# 5V_Source.net
KiCad netlist of a schematic drawn in Altium Designer
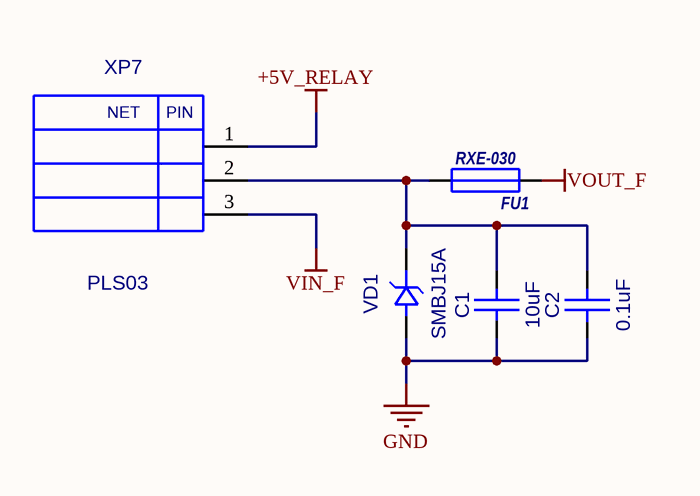
[diagram p0: 5V_Source.SchDoc]

(export (version "E")
  (design (tool "Eeschema 10.0.6"))
  (components
    (comp (ref "C1")
      (value "10uF")
      (footprint "CC0805")
      (description "CC0805")
      (libsource (lib "gprs_modem_2") (part "CC0805"))
    )
    (comp (ref "C2")
      (value "0.1uF")
      (footprint "CC0603")
      (description "CC0603")
      (libsource (lib "gprs_modem_2") (part "CC0603"))
    )
    (comp (ref "FU1")
      (value "RXE-030")
      (footprint "RXE-110")
      (description "RXE-110")
      (libsource (lib "gprs_modem_2") (part "RXE-110"))
    )
    (comp (ref "VD1")
      (value "SMBJ15A")
      (footprint "SMB")
      (description "SMBJ")
      (libsource (lib "gprs_modem_2") (part "SMBJ"))
    )
    (comp (ref "XP7") (value "PLS03") (footprint "PLS-03") (libsource (lib "gprs_modem_2") (part "PLS03")))
  )
  (nets
    (net (code "1") (name "+5V_RELAY") (class "Default")
      (node (ref "XP7") (pin "1") (pinfunction "1_1") (pintype "passive"))
    )
    (net (code "2") (name "GND") (class "Default")
      (node (ref "C1") (pin "1") (pinfunction "A_1") (pintype "passive"))
      (node (ref "C2") (pin "1") (pinfunction "A_1") (pintype "passive"))
      (node (ref "VD1") (pin "1") (pinfunction "A_1") (pintype "passive"))
    )
    (net (code "3") (name "Net-(C1-B)") (class "Default")
      (node (ref "C1") (pin "2") (pinfunction "B_2") (pintype "passive"))
      (node (ref "C2") (pin "2") (pinfunction "B_2") (pintype "passive"))
      (node (ref "FU1") (pin "2") (pintype "passive"))
      (node (ref "VD1") (pin "2") (pinfunction "K_2") (pintype "passive"))
      (node (ref "XP7") (pin "2") (pinfunction "2_2") (pintype "passive"))
    )
    (net (code "4") (name "VIN_F") (class "Default")
      (node (ref "XP7") (pin "3") (pinfunction "3_3") (pintype "passive"))
    )
    (net (code "5") (name "VOUT_F") (class "Default") (node (ref "FU1") (pin "1") (pintype "passive")))
  )
)
